# Practica1.net
KiCad netlist of a schematic drawn in EAGLE
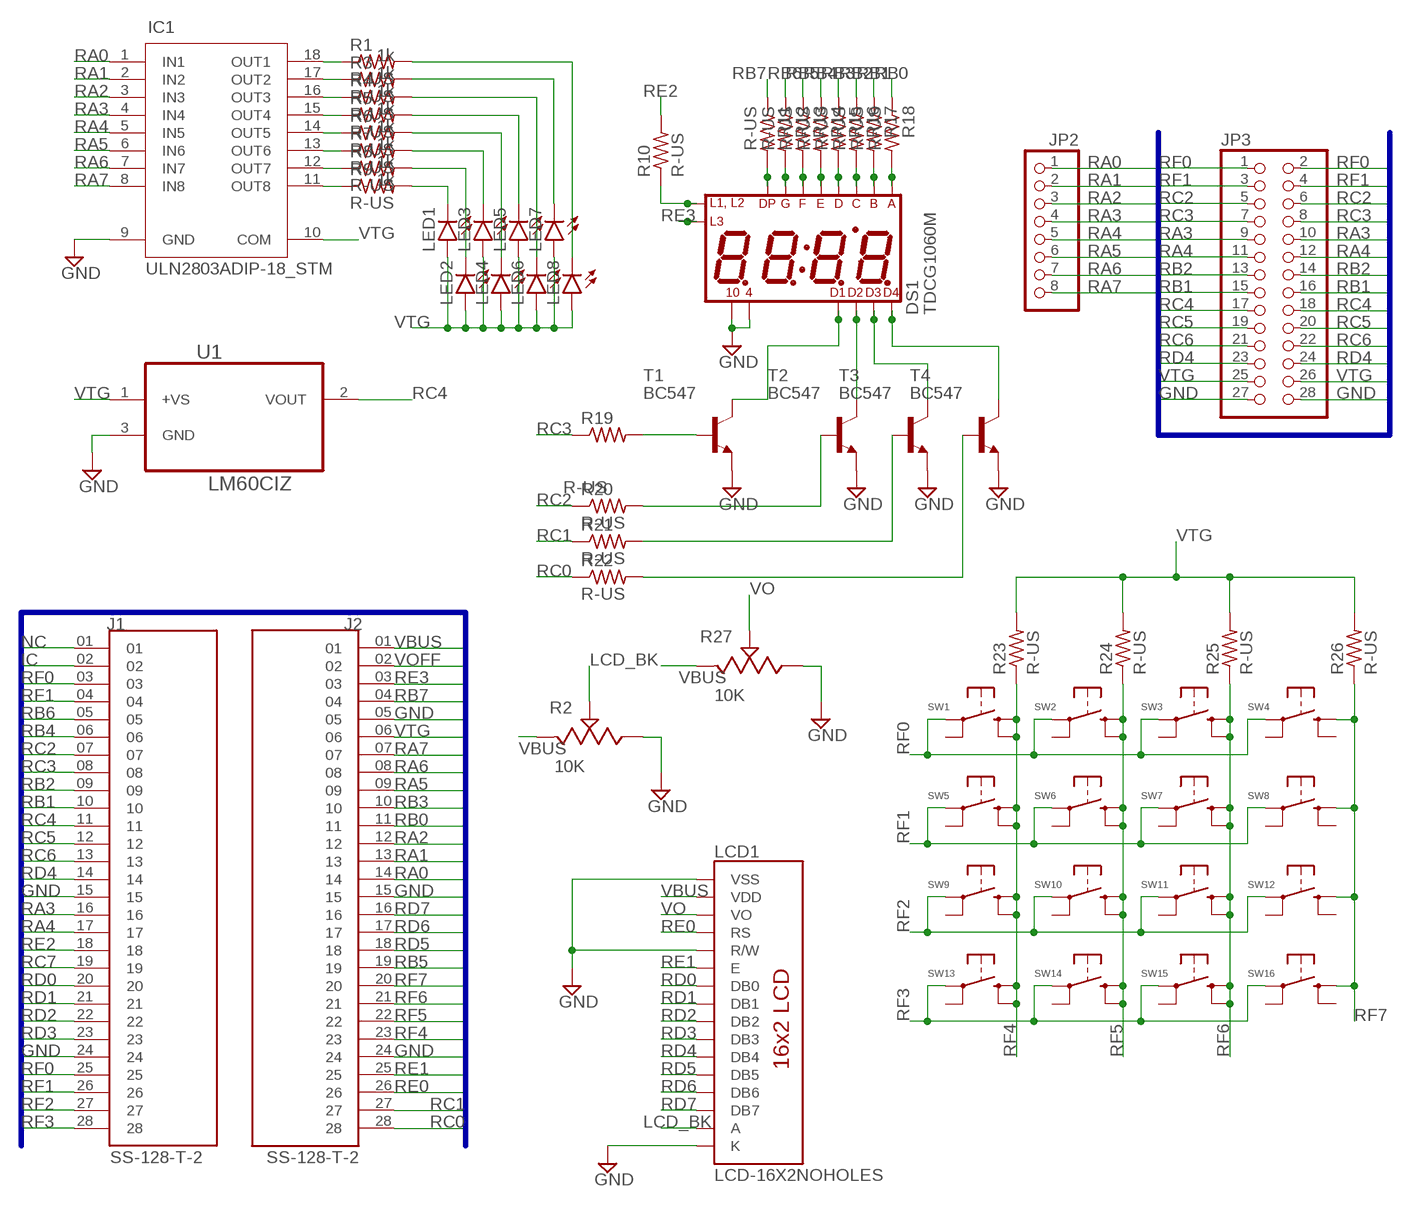
[diagram p0: schematic, sheet 1]

(export (version "E")
  (design (tool "Eeschema 10.0.6"))
  (components
    (comp (ref "DS1")
      (value "TDCG1060M")
      (footprint "eagle-import:DISPLAY_TDCG1060M")
      (fields (field (name "DIGI-KEY_PART_NUMBER") "TDCG1060M-ND") (field (name "MF") "Vishay"))
      (libsource (lib "eagle-import") (part "TDCG1060M"))
    )
    (comp (ref "IC1")
      (value "ULN2803ADIP-18_STM")
      (footprint "eagle-import:DIP-18_STM")
      (fields
        (field (name "MANUFACTURER_PART_NUMBER") "ULN2803A")
        (field (name "COPYRIGHT") "Copyright (C) 2022 Ultra Librarian. All rights reserved.")
      )
      (libsource (lib "eagle-import") (part "ULN2803ADIP-18_STM"))
    )
    (comp (ref "J1")
      (value "SS-128-T-2")
      (footprint "eagle-import:SAMTEC_SS-128-T-2")
      (fields (field (name "DIGI-KEY_PART_NUMBER") "SAM1117-28-ND") (field (name "MF") "Samtec"))
      (libsource (lib "eagle-import") (part "SS-128-T-2"))
    )
    (comp (ref "J2")
      (value "SS-128-T-2")
      (footprint "eagle-import:SAMTEC_SS-128-T-2")
      (fields (field (name "DIGI-KEY_PART_NUMBER") "SAM1117-28-ND") (field (name "MF") "Samtec"))
      (libsource (lib "eagle-import") (part "SS-128-T-2"))
    )
    (comp (ref "JP2")
      (value "PINHD-1X8BIG")
      (footprint "eagle-import:1X08-BIG")
      (libsource (lib "eagle-import") (part "PINHD-1X8BIG"))
    )
    (comp (ref "JP3")
      (value "PINHD-2X14")
      (footprint "eagle-import:2X14")
      (libsource (lib "eagle-import") (part "PINHD-2X14"))
    )
    (comp (ref "LCD1")
      (value "LCD-16X2NOHOLES")
      (footprint "eagle-import:LCD-16X2_NOHOLESNOSILK")
      (libsource (lib "eagle-import") (part "LCD-16X2NOHOLES"))
    )
    (comp (ref "LED1")
      (value "LED3MM")
      (footprint "eagle-import:LED3MM")
      (libsource (lib "eagle-import") (part "LED3MM"))
    )
    (comp (ref "LED2")
      (value "LED3MM")
      (footprint "eagle-import:LED3MM")
      (libsource (lib "eagle-import") (part "LED3MM"))
    )
    (comp (ref "LED3")
      (value "LED3MM")
      (footprint "eagle-import:LED3MM")
      (libsource (lib "eagle-import") (part "LED3MM"))
    )
    (comp (ref "LED4")
      (value "LED3MM")
      (footprint "eagle-import:LED3MM")
      (libsource (lib "eagle-import") (part "LED3MM"))
    )
    (comp (ref "LED5")
      (value "LED3MM")
      (footprint "eagle-import:LED3MM")
      (libsource (lib "eagle-import") (part "LED3MM"))
    )
    (comp (ref "LED6")
      (value "LED3MM")
      (footprint "eagle-import:LED3MM")
      (libsource (lib "eagle-import") (part "LED3MM"))
    )
    (comp (ref "LED7")
      (value "LED3MM")
      (footprint "eagle-import:LED3MM")
      (libsource (lib "eagle-import") (part "LED3MM"))
    )
    (comp (ref "LED8")
      (value "LED3MM")
      (footprint "eagle-import:LED3MM")
      (libsource (lib "eagle-import") (part "LED3MM"))
    )
    (comp (ref "R1")
      (value "R-US")
      (footprint "eagle-import:0207_10")
      (fields (field (name "SPICEPREFIX") "R") (field (name "SPICEPREFIX_1") "1k"))
      (libsource (lib "eagle-import") (part "R-US"))
    )
    (comp (ref "R2")
      (value "10K")
      (footprint "eagle-import:3362P-1-103LF")
      (fields
        (field (name "MANUFACTURER") "Bourns Inc.")
        (field (name "MPN") "3362P-1-103LF")
        (field (name "CREATED_PN") "PCBLayout.com")
      )
      (libsource (lib "eagle-import") (part "3362P-1-103LF"))
    )
    (comp (ref "R3")
      (value "R-US")
      (footprint "eagle-import:0207_10")
      (fields (field (name "SPICEPREFIX") "R") (field (name "SPICEPREFIX_1") "1k"))
      (libsource (lib "eagle-import") (part "R-US"))
    )
    (comp (ref "R4")
      (value "R-US")
      (footprint "eagle-import:0207_10")
      (fields (field (name "SPICEPREFIX") "R") (field (name "SPICEPREFIX_1") "1k"))
      (libsource (lib "eagle-import") (part "R-US"))
    )
    (comp (ref "R5")
      (value "R-US")
      (footprint "eagle-import:0207_10")
      (fields (field (name "SPICEPREFIX") "R") (field (name "SPICEPREFIX_1") "1k"))
      (libsource (lib "eagle-import") (part "R-US"))
    )
    (comp (ref "R6")
      (value "R-US")
      (footprint "eagle-import:0207_10")
      (fields (field (name "SPICEPREFIX") "R") (field (name "SPICEPREFIX_1") "1k"))
      (libsource (lib "eagle-import") (part "R-US"))
    )
    (comp (ref "R7")
      (value "R-US")
      (footprint "eagle-import:0207_10")
      (fields (field (name "SPICEPREFIX") "R") (field (name "SPICEPREFIX_1") "1k"))
      (libsource (lib "eagle-import") (part "R-US"))
    )
    (comp (ref "R8")
      (value "R-US")
      (footprint "eagle-import:0207_10")
      (fields (field (name "SPICEPREFIX") "R") (field (name "SPICEPREFIX_1") "1k"))
      (libsource (lib "eagle-import") (part "R-US"))
    )
    (comp (ref "R9")
      (value "R-US")
      (footprint "eagle-import:0207_10")
      (fields (field (name "SPICEPREFIX") "R") (field (name "SPICEPREFIX_1") "1k"))
      (libsource (lib "eagle-import") (part "R-US"))
    )
    (comp (ref "R10")
      (value "R-US")
      (footprint "eagle-import:0207_10")
      (fields (field (name "SPICEPREFIX") "130"))
      (libsource (lib "eagle-import") (part "R-US"))
    )
    (comp (ref "R11")
      (value "R-US")
      (footprint "eagle-import:0207_10")
      (fields (field (name "SPICEPREFIX") "130"))
      (libsource (lib "eagle-import") (part "R-US"))
    )
    (comp (ref "R12")
      (value "R-US")
      (footprint "eagle-import:0207_10")
      (fields (field (name "SPICEPREFIX") "130"))
      (libsource (lib "eagle-import") (part "R-US"))
    )
    (comp (ref "R13")
      (value "R-US")
      (footprint "eagle-import:0207_10")
      (fields (field (name "SPICEPREFIX") "130"))
      (libsource (lib "eagle-import") (part "R-US"))
    )
    (comp (ref "R14")
      (value "R-US")
      (footprint "eagle-import:0207_10")
      (fields (field (name "SPICEPREFIX") "130"))
      (libsource (lib "eagle-import") (part "R-US"))
    )
    (comp (ref "R15")
      (value "R-US")
      (footprint "eagle-import:0207_10")
      (fields (field (name "SPICEPREFIX") "130"))
      (libsource (lib "eagle-import") (part "R-US"))
    )
    (comp (ref "R16")
      (value "R-US")
      (footprint "eagle-import:0207_10")
      (fields (field (name "SPICEPREFIX") "130"))
      (libsource (lib "eagle-import") (part "R-US"))
    )
    (comp (ref "R17")
      (value "R-US")
      (footprint "eagle-import:0207_10")
      (fields (field (name "SPICEPREFIX") "130"))
      (libsource (lib "eagle-import") (part "R-US"))
    )
    (comp (ref "R18")
      (value "R-US")
      (footprint "eagle-import:0207_10")
      (fields (field (name "SPICEPREFIX") "130"))
      (libsource (lib "eagle-import") (part "R-US"))
    )
    (comp (ref "R19")
      (value "R-US")
      (footprint "eagle-import:0207_10")
      (fields (field (name "SPICEPREFIX") "52K"))
      (libsource (lib "eagle-import") (part "R-US"))
    )
    (comp (ref "R20")
      (value "R-US")
      (footprint "eagle-import:0207_10")
      (fields (field (name "SPICEPREFIX") "52K"))
      (libsource (lib "eagle-import") (part "R-US"))
    )
    (comp (ref "R21")
      (value "R-US")
      (footprint "eagle-import:0207_10")
      (fields (field (name "SPICEPREFIX") "52K"))
      (libsource (lib "eagle-import") (part "R-US"))
    )
    (comp (ref "R22")
      (value "R-US")
      (footprint "eagle-import:0207_10")
      (fields (field (name "SPICEPREFIX") "52K"))
      (libsource (lib "eagle-import") (part "R-US"))
    )
    (comp (ref "R23")
      (value "R-US")
      (footprint "eagle-import:0207_10")
      (fields (field (name "SPICEPREFIX") "1K"))
      (libsource (lib "eagle-import") (part "R-US"))
    )
    (comp (ref "R24")
      (value "R-US")
      (footprint "eagle-import:0207_10")
      (fields (field (name "SPICEPREFIX") "1K"))
      (libsource (lib "eagle-import") (part "R-US"))
    )
    (comp (ref "R25")
      (value "R-US")
      (footprint "eagle-import:0207_10")
      (fields (field (name "SPICEPREFIX") "1K"))
      (libsource (lib "eagle-import") (part "R-US"))
    )
    (comp (ref "R26")
      (value "R-US")
      (footprint "eagle-import:0207_10")
      (fields (field (name "SPICEPREFIX") "1K"))
      (libsource (lib "eagle-import") (part "R-US"))
    )
    (comp (ref "R27")
      (value "10K")
      (footprint "eagle-import:3362P-1-103LF")
      (fields
        (field (name "MANUFACTURER") "Bourns Inc.")
        (field (name "MPN") "3362P-1-103LF")
        (field (name "CREATED_PN") "PCBLayout.com")
      )
      (libsource (lib "eagle-import") (part "3362P-1-103LF"))
    )
    (comp (ref "SW1")
      (value "1825910-2")
      (footprint "eagle-import:TE_1825910-2")
      (fields (field (name "MF") "TE Connectivity"))
      (libsource (lib "eagle-import") (part "1825910-2"))
    )
    (comp (ref "SW2")
      (value "1825910-2")
      (footprint "eagle-import:TE_1825910-2")
      (fields (field (name "MF") "TE Connectivity"))
      (libsource (lib "eagle-import") (part "1825910-2"))
    )
    (comp (ref "SW3")
      (value "1825910-2")
      (footprint "eagle-import:TE_1825910-2")
      (fields (field (name "MF") "TE Connectivity"))
      (libsource (lib "eagle-import") (part "1825910-2"))
    )
    (comp (ref "SW4")
      (value "1825910-2")
      (footprint "eagle-import:TE_1825910-2")
      (fields (field (name "MF") "TE Connectivity"))
      (libsource (lib "eagle-import") (part "1825910-2"))
    )
    (comp (ref "SW5")
      (value "1825910-2")
      (footprint "eagle-import:TE_1825910-2")
      (fields (field (name "MF") "TE Connectivity"))
      (libsource (lib "eagle-import") (part "1825910-2"))
    )
    (comp (ref "SW6")
      (value "1825910-2")
      (footprint "eagle-import:TE_1825910-2")
      (fields (field (name "MF") "TE Connectivity"))
      (libsource (lib "eagle-import") (part "1825910-2"))
    )
    (comp (ref "SW7")
      (value "1825910-2")
      (footprint "eagle-import:TE_1825910-2")
      (fields (field (name "MF") "TE Connectivity"))
      (libsource (lib "eagle-import") (part "1825910-2"))
    )
    (comp (ref "SW8")
      (value "1825910-2")
      (footprint "eagle-import:TE_1825910-2")
      (fields (field (name "MF") "TE Connectivity"))
      (libsource (lib "eagle-import") (part "1825910-2"))
    )
    (comp (ref "SW9")
      (value "1825910-2")
      (footprint "eagle-import:TE_1825910-2")
      (fields (field (name "MF") "TE Connectivity"))
      (libsource (lib "eagle-import") (part "1825910-2"))
    )
    (comp (ref "SW10")
      (value "1825910-2")
      (footprint "eagle-import:TE_1825910-2")
      (fields (field (name "MF") "TE Connectivity"))
      (libsource (lib "eagle-import") (part "1825910-2"))
    )
    (comp (ref "SW11")
      (value "1825910-2")
      (footprint "eagle-import:TE_1825910-2")
      (fields (field (name "MF") "TE Connectivity"))
      (libsource (lib "eagle-import") (part "1825910-2"))
    )
    (comp (ref "SW12")
      (value "1825910-2")
      (footprint "eagle-import:TE_1825910-2")
      (fields (field (name "MF") "TE Connectivity"))
      (libsource (lib "eagle-import") (part "1825910-2"))
    )
    (comp (ref "SW13")
      (value "1825910-2")
      (footprint "eagle-import:TE_1825910-2")
      (fields (field (name "MF") "TE Connectivity"))
      (libsource (lib "eagle-import") (part "1825910-2"))
    )
    (comp (ref "SW14")
      (value "1825910-2")
      (footprint "eagle-import:TE_1825910-2")
      (fields (field (name "MF") "TE Connectivity"))
      (libsource (lib "eagle-import") (part "1825910-2"))
    )
    (comp (ref "SW15")
      (value "1825910-2")
      (footprint "eagle-import:TE_1825910-2")
      (fields (field (name "MF") "TE Connectivity"))
      (libsource (lib "eagle-import") (part "1825910-2"))
    )
    (comp (ref "SW16")
      (value "1825910-2")
      (footprint "eagle-import:TE_1825910-2")
      (fields (field (name "MF") "TE Connectivity"))
      (libsource (lib "eagle-import") (part "1825910-2"))
    )
    (comp (ref "T1")
      (value "BC547")
      (footprint "eagle-import:TO92")
      (libsource (lib "eagle-import") (part "BC547"))
    )
    (comp (ref "T2")
      (value "BC547")
      (footprint "eagle-import:TO92")
      (libsource (lib "eagle-import") (part "BC547"))
    )
    (comp (ref "T3")
      (value "BC547")
      (footprint "eagle-import:TO92")
      (libsource (lib "eagle-import") (part "BC547"))
    )
    (comp (ref "T4")
      (value "BC547")
      (footprint "eagle-import:TO92")
      (libsource (lib "eagle-import") (part "BC547"))
    )
    (comp (ref "U1")
      (value "LM60CIZ")
      (footprint "eagle-import:TO92_")
      (libsource (lib "eagle-import") (part "LM60CIZ"))
    )
  )
  (nets
    (net (code "1") (name "/IC") (class "Default")
      (node (ref "J1") (pin "02") (pinfunction "02_02") (pintype "passive"))
    )
    (net (code "2") (name "/LCD_BK") (class "Default")
      (node (ref "LCD1") (pin "15") (pinfunction "A_15") (pintype "power_in"))
      (node (ref "R2") (pin "2") (pinfunction "2_2") (pintype "passive"))
    )
    (net (code "3") (name "/NC") (class "Default")
      (node (ref "J1") (pin "01") (pinfunction "01_01") (pintype "passive"))
    )
    (net (code "4") (name "/RA0") (class "Default")
      (node (ref "IC1") (pin "1") (pinfunction "IN1_1") (pintype "input"))
      (node (ref "J2") (pin "14") (pinfunction "14_14") (pintype "passive"))
      (node (ref "JP2") (pin "1") (pinfunction "1_1") (pintype "passive"))
    )
    (net (code "5") (name "/RA1") (class "Default")
      (node (ref "IC1") (pin "2") (pinfunction "IN2_2") (pintype "input"))
      (node (ref "J2") (pin "13") (pinfunction "13_13") (pintype "passive"))
      (node (ref "JP2") (pin "2") (pinfunction "2_2") (pintype "passive"))
    )
    (net (code "6") (name "/RA2") (class "Default")
      (node (ref "IC1") (pin "3") (pinfunction "IN3_3") (pintype "input"))
      (node (ref "J2") (pin "12") (pinfunction "12_12") (pintype "passive"))
      (node (ref "JP2") (pin "3") (pinfunction "3_3") (pintype "passive"))
    )
    (net (code "7") (name "/RA3") (class "Default")
      (node (ref "IC1") (pin "4") (pinfunction "IN4_4") (pintype "input"))
      (node (ref "J1") (pin "16") (pinfunction "16_16") (pintype "passive"))
      (node (ref "JP2") (pin "4") (pinfunction "4_4") (pintype "passive"))
      (node (ref "JP3") (pin "10") (pinfunction "10_10") (pintype "passive"))
      (node (ref "JP3") (pin "9") (pinfunction "9_9") (pintype "passive"))
    )
    (net (code "8") (name "/RA4") (class "Default")
      (node (ref "IC1") (pin "5") (pinfunction "IN5_5") (pintype "input"))
      (node (ref "J1") (pin "17") (pinfunction "17_17") (pintype "passive"))
      (node (ref "JP2") (pin "5") (pinfunction "5_5") (pintype "passive"))
      (node (ref "JP3") (pin "11") (pinfunction "11_11") (pintype "passive"))
      (node (ref "JP3") (pin "12") (pinfunction "12_12") (pintype "passive"))
    )
    (net (code "9") (name "/RA5") (class "Default")
      (node (ref "IC1") (pin "6") (pinfunction "IN6_6") (pintype "input"))
      (node (ref "J2") (pin "09") (pinfunction "09_09") (pintype "passive"))
      (node (ref "JP2") (pin "6") (pinfunction "6_6") (pintype "passive"))
    )
    (net (code "10") (name "/RA6") (class "Default")
      (node (ref "IC1") (pin "7") (pinfunction "IN7_7") (pintype "input"))
      (node (ref "J2") (pin "08") (pinfunction "08_08") (pintype "passive"))
      (node (ref "JP2") (pin "7") (pinfunction "7_7") (pintype "passive"))
    )
    (net (code "11") (name "/RA7") (class "Default")
      (node (ref "IC1") (pin "8") (pinfunction "IN8_8") (pintype "input"))
      (node (ref "J2") (pin "07") (pinfunction "07_07") (pintype "passive"))
      (node (ref "JP2") (pin "8") (pinfunction "8_8") (pintype "passive"))
    )
    (net (code "12") (name "/RB0") (class "Default")
      (node (ref "J2") (pin "11") (pinfunction "11_11") (pintype "passive"))
      (node (ref "R18") (pin "1") (pinfunction "1_1") (pintype "passive"))
    )
    (net (code "13") (name "/RB1") (class "Default")
      (node (ref "J1") (pin "10") (pinfunction "10_10") (pintype "passive"))
      (node (ref "JP3") (pin "15") (pinfunction "15_15") (pintype "passive"))
      (node (ref "JP3") (pin "16") (pinfunction "16_16") (pintype "passive"))
      (node (ref "R17") (pin "1") (pinfunction "1_1") (pintype "passive"))
    )
    (net (code "14") (name "/RB2") (class "Default")
      (node (ref "J1") (pin "09") (pinfunction "09_09") (pintype "passive"))
      (node (ref "JP3") (pin "13") (pinfunction "13_13") (pintype "passive"))
      (node (ref "JP3") (pin "14") (pinfunction "14_14") (pintype "passive"))
      (node (ref "R16") (pin "1") (pinfunction "1_1") (pintype "passive"))
    )
    (net (code "15") (name "/RB3") (class "Default")
      (node (ref "J2") (pin "10") (pinfunction "10_10") (pintype "passive"))
      (node (ref "R15") (pin "1") (pinfunction "1_1") (pintype "passive"))
    )
    (net (code "16") (name "/RB4") (class "Default")
      (node (ref "J1") (pin "06") (pinfunction "06_06") (pintype "passive"))
      (node (ref "R14") (pin "1") (pinfunction "1_1") (pintype "passive"))
    )
    (net (code "17") (name "/RB5") (class "Default")
      (node (ref "J2") (pin "19") (pinfunction "19_19") (pintype "passive"))
      (node (ref "R13") (pin "1") (pinfunction "1_1") (pintype "passive"))
    )
    (net (code "18") (name "/RB6") (class "Default")
      (node (ref "J1") (pin "05") (pinfunction "05_05") (pintype "passive"))
      (node (ref "R12") (pin "1") (pinfunction "1_1") (pintype "passive"))
    )
    (net (code "19") (name "/RB7") (class "Default")
      (node (ref "J2") (pin "04") (pinfunction "04_04") (pintype "passive"))
      (node (ref "R11") (pin "1") (pinfunction "1_1") (pintype "passive"))
    )
    (net (code "20") (name "/RC0") (class "Default")
      (node (ref "J2") (pin "28") (pinfunction "28_28") (pintype "passive"))
      (node (ref "R22") (pin "1") (pinfunction "1_1") (pintype "passive"))
    )
    (net (code "21") (name "/RC1") (class "Default")
      (node (ref "J2") (pin "27") (pinfunction "27_27") (pintype "passive"))
      (node (ref "R21") (pin "1") (pinfunction "1_1") (pintype "passive"))
    )
    (net (code "22") (name "/RC2") (class "Default")
      (node (ref "J1") (pin "07") (pinfunction "07_07") (pintype "passive"))
      (node (ref "JP3") (pin "5") (pinfunction "5_5") (pintype "passive"))
      (node (ref "JP3") (pin "6") (pinfunction "6_6") (pintype "passive"))
      (node (ref "R20") (pin "1") (pinfunction "1_1") (pintype "passive"))
    )
    (net (code "23") (name "/RC3") (class "Default")
      (node (ref "J1") (pin "08") (pinfunction "08_08") (pintype "passive"))
      (node (ref "JP3") (pin "7") (pinfunction "7_7") (pintype "passive"))
      (node (ref "JP3") (pin "8") (pinfunction "8_8") (pintype "passive"))
      (node (ref "R19") (pin "1") (pinfunction "1_1") (pintype "passive"))
    )
    (net (code "24") (name "/RC4") (class "Default")
      (node (ref "J1") (pin "11") (pinfunction "11_11") (pintype "passive"))
      (node (ref "JP3") (pin "17") (pinfunction "17_17") (pintype "passive"))
      (node (ref "JP3") (pin "18") (pinfunction "18_18") (pintype "passive"))
      (node (ref "U1") (pin "2") (pinfunction "VOUT_2") (pintype "output"))
    )
    (net (code "25") (name "/RC5") (class "Default")
      (node (ref "J1") (pin "12") (pinfunction "12_12") (pintype "passive"))
      (node (ref "JP3") (pin "19") (pinfunction "19_19") (pintype "passive"))
      (node (ref "JP3") (pin "20") (pinfunction "20_20") (pintype "passive"))
    )
    (net (code "26") (name "/RC6") (class "Default")
      (node (ref "J1") (pin "13") (pinfunction "13_13") (pintype "passive"))
      (node (ref "JP3") (pin "21") (pinfunction "21_21") (pintype "passive"))
      (node (ref "JP3") (pin "22") (pinfunction "22_22") (pintype "passive"))
    )
    (net (code "27") (name "/RC7") (class "Default")
      (node (ref "J1") (pin "19") (pinfunction "19_19") (pintype "passive"))
    )
    (net (code "28") (name "/RD0") (class "Default")
      (node (ref "J1") (pin "20") (pinfunction "20_20") (pintype "passive"))
      (node (ref "LCD1") (pin "7") (pinfunction "DB0_7") (pintype "bidirectional"))
    )
    (net (code "29") (name "/RD1") (class "Default")
      (node (ref "J1") (pin "21") (pinfunction "21_21") (pintype "passive"))
      (node (ref "LCD1") (pin "8") (pinfunction "DB1_8") (pintype "bidirectional"))
    )
    (net (code "30") (name "/RD2") (class "Default")
      (node (ref "J1") (pin "22") (pinfunction "22_22") (pintype "passive"))
      (node (ref "LCD1") (pin "9") (pinfunction "DB2_9") (pintype "bidirectional"))
    )
    (net (code "31") (name "/RD3") (class "Default")
      (node (ref "J1") (pin "23") (pinfunction "23_23") (pintype "passive"))
      (node (ref "LCD1") (pin "10") (pinfunction "DB3_10") (pintype "bidirectional"))
    )
    (net (code "32") (name "/RD4") (class "Default")
      (node (ref "J1") (pin "14") (pinfunction "14_14") (pintype "passive"))
      (node (ref "JP3") (pin "23") (pinfunction "23_23") (pintype "passive"))
      (node (ref "JP3") (pin "24") (pinfunction "24_24") (pintype "passive"))
      (node (ref "LCD1") (pin "11") (pinfunction "DB4_11") (pintype "bidirectional"))
    )
    (net (code "33") (name "/RD5") (class "Default")
      (node (ref "J2") (pin "18") (pinfunction "18_18") (pintype "passive"))
      (node (ref "LCD1") (pin "12") (pinfunction "DB5_12") (pintype "bidirectional"))
    )
    (net (code "34") (name "/RD6") (class "Default")
      (node (ref "J2") (pin "17") (pinfunction "17_17") (pintype "passive"))
      (node (ref "LCD1") (pin "13") (pinfunction "DB6_13") (pintype "bidirectional"))
    )
    (net (code "35") (name "/RD7") (class "Default")
      (node (ref "J2") (pin "16") (pinfunction "16_16") (pintype "passive"))
      (node (ref "LCD1") (pin "14") (pinfunction "DB7_14") (pintype "bidirectional"))
    )
    (net (code "36") (name "/RE0") (class "Default")
      (node (ref "J2") (pin "26") (pinfunction "26_26") (pintype "passive"))
      (node (ref "LCD1") (pin "4") (pinfunction "RS_4") (pintype "input"))
    )
    (net (code "37") (name "/RE1") (class "Default")
      (node (ref "J2") (pin "25") (pinfunction "25_25") (pintype "passive"))
      (node (ref "LCD1") (pin "6") (pinfunction "E_6") (pintype "input"))
    )
    (net (code "38") (name "/RE2") (class "Default")
      (node (ref "J1") (pin "18") (pinfunction "18_18") (pintype "passive"))
      (node (ref "R10") (pin "2") (pinfunction "2_2") (pintype "passive"))
    )
    (net (code "39") (name "/RE3") (class "Default")
      (node (ref "DS1") (pin "9") (pinfunction "L3_9") (pintype "passive"))
      (node (ref "J2") (pin "03") (pinfunction "03_03") (pintype "passive"))
    )
    (net (code "40") (name "/RF0") (class "Default")
      (node (ref "J1") (pin "03") (pinfunction "03_03") (pintype "passive"))
      (node (ref "J1") (pin "25") (pinfunction "25_25") (pintype "passive"))
      (node (ref "JP3") (pin "1") (pinfunction "1_1") (pintype "passive"))
      (node (ref "JP3") (pin "2") (pinfunction "2_2") (pintype "passive"))
      (node (ref "SW1") (pin "1") (pinfunction "P_1") (pintype "passive"))
      (node (ref "SW2") (pin "1") (pinfunction "P_1") (pintype "passive"))
      (node (ref "SW3") (pin "1") (pinfunction "P_1") (pintype "passive"))
      (node (ref "SW4") (pin "1") (pinfunction "P_1") (pintype "passive"))
    )
    (net (code "41") (name "/RF1") (class "Default")
      (node (ref "J1") (pin "04") (pinfunction "04_04") (pintype "passive"))
      (node (ref "J1") (pin "26") (pinfunction "26_26") (pintype "passive"))
      (node (ref "JP3") (pin "3") (pinfunction "3_3") (pintype "passive"))
      (node (ref "JP3") (pin "4") (pinfunction "4_4") (pintype "passive"))
      (node (ref "SW5") (pin "1") (pinfunction "P_1") (pintype "passive"))
      (node (ref "SW6") (pin "1") (pinfunction "P_1") (pintype "passive"))
      (node (ref "SW7") (pin "1") (pinfunction "P_1") (pintype "passive"))
      (node (ref "SW8") (pin "1") (pinfunction "P_1") (pintype "passive"))
    )
    (net (code "42") (name "/RF2") (class "Default")
      (node (ref "J1") (pin "27") (pinfunction "27_27") (pintype "passive"))
      (node (ref "SW10") (pin "1") (pinfunction "P_1") (pintype "passive"))
      (node (ref "SW11") (pin "1") (pinfunction "P_1") (pintype "passive"))
      (node (ref "SW12") (pin "1") (pinfunction "P_1") (pintype "passive"))
      (node (ref "SW9") (pin "1") (pinfunction "P_1") (pintype "passive"))
    )
    (net (code "43") (name "/RF3") (class "Default")
      (node (ref "J1") (pin "28") (pinfunction "28_28") (pintype "passive"))
      (node (ref "SW13") (pin "1") (pinfunction "P_1") (pintype "passive"))
      (node (ref "SW14") (pin "1") (pinfunction "P_1") (pintype "passive"))
      (node (ref "SW15") (pin "1") (pinfunction "P_1") (pintype "passive"))
      (node (ref "SW16") (pin "1") (pinfunction "P_1") (pintype "passive"))
    )
    (net (code "44") (name "/RF4") (class "Default")
      (node (ref "J2") (pin "23") (pinfunction "23_23") (pintype "passive"))
      (node (ref "R23") (pin "1") (pinfunction "1_1") (pintype "passive"))
      (node (ref "SW1") (pin "2") (pinfunction "S_2") (pintype "passive"))
      (node (ref "SW1") (pin "4") (pinfunction "S1_4") (pintype "passive"))
      (node (ref "SW13") (pin "2") (pinfunction "S_2") (pintype "passive"))
      (node (ref "SW13") (pin "4") (pinfunction "S1_4") (pintype "passive"))
      (node (ref "SW5") (pin "2") (pinfunction "S_2") (pintype "passive"))
      (node (ref "SW5") (pin "4") (pinfunction "S1_4") (pintype "passive"))
      (node (ref "SW9") (pin "2") (pinfunction "S_2") (pintype "passive"))
      (node (ref "SW9") (pin "4") (pinfunction "S1_4") (pintype "passive"))
    )
    (net (code "45") (name "/RF5") (class "Default")
      (node (ref "J2") (pin "22") (pinfunction "22_22") (pintype "passive"))
      (node (ref "R24") (pin "1") (pinfunction "1_1") (pintype "passive"))
      (node (ref "SW10") (pin "2") (pinfunction "S_2") (pintype "passive"))
      (node (ref "SW10") (pin "4") (pinfunction "S1_4") (pintype "passive"))
      (node (ref "SW14") (pin "2") (pinfunction "S_2") (pintype "passive"))
      (node (ref "SW14") (pin "4") (pinfunction "S1_4") (pintype "passive"))
      (node (ref "SW2") (pin "2") (pinfunction "S_2") (pintype "passive"))
      (node (ref "SW2") (pin "4") (pinfunction "S1_4") (pintype "passive"))
      (node (ref "SW6") (pin "2") (pinfunction "S_2") (pintype "passive"))
      (node (ref "SW6") (pin "4") (pinfunction "S1_4") (pintype "passive"))
    )
    (net (code "46") (name "/RF6") (class "Default")
      (node (ref "J2") (pin "21") (pinfunction "21_21") (pintype "passive"))
      (node (ref "R25") (pin "1") (pinfunction "1_1") (pintype "passive"))
      (node (ref "SW11") (pin "2") (pinfunction "S_2") (pintype "passive"))
      (node (ref "SW11") (pin "4") (pinfunction "S1_4") (pintype "passive"))
      (node (ref "SW15") (pin "2") (pinfunction "S_2") (pintype "passive"))
      (node (ref "SW15") (pin "4") (pinfunction "S1_4") (pintype "passive"))
      (node (ref "SW3") (pin "2") (pinfunction "S_2") (pintype "passive"))
      (node (ref "SW3") (pin "4") (pinfunction "S1_4") (pintype "passive"))
      (node (ref "SW7") (pin "2") (pinfunction "S_2") (pintype "passive"))
      (node (ref "SW7") (pin "4") (pinfunction "S1_4") (pintype "passive"))
    )
    (net (code "47") (name "/RF7") (class "Default")
      (node (ref "J2") (pin "20") (pinfunction "20_20") (pintype "passive"))
      (node (ref "R26") (pin "1") (pinfunction "1_1") (pintype "passive"))
      (node (ref "SW12") (pin "2") (pinfunction "S_2") (pintype "passive"))
      (node (ref "SW16") (pin "2") (pinfunction "S_2") (pintype "passive"))
      (node (ref "SW4") (pin "2") (pinfunction "S_2") (pintype "passive"))
      (node (ref "SW8") (pin "2") (pinfunction "S_2") (pintype "passive"))
    )
    (net (code "48") (name "/VBUS") (class "Default")
      (node (ref "J2") (pin "01") (pinfunction "01_01") (pintype "passive"))
      (node (ref "LCD1") (pin "2") (pinfunction "VDD_2") (pintype "power_in"))
      (node (ref "R2") (pin "1") (pinfunction "1_1") (pintype "passive"))
      (node (ref "R27") (pin "1") (pinfunction "1_1") (pintype "passive"))
    )
    (net (code "49") (name "/VO") (class "Default")
      (node (ref "LCD1") (pin "3") (pinfunction "VO_3") (pintype "bidirectional"))
      (node (ref "R27") (pin "2") (pinfunction "2_2") (pintype "passive"))
    )
    (net (code "50") (name "/VOFF") (class "Default")
      (node (ref "J2") (pin "02") (pinfunction "02_02") (pintype "passive"))
    )
    (net (code "51") (name "/VTG") (class "Default")
      (node (ref "IC1") (pin "10") (pinfunction "COM_10") (pintype "passive"))
      (node (ref "J2") (pin "06") (pinfunction "06_06") (pintype "passive"))
      (node (ref "JP3") (pin "25") (pinfunction "25_25") (pintype "passive"))
      (node (ref "JP3") (pin "26") (pinfunction "26_26") (pintype "passive"))
      (node (ref "LED1") (pin "A") (pinfunction "A_A") (pintype "passive"))
      (node (ref "LED2") (pin "A") (pinfunction "A_A") (pintype "passive"))
      (node (ref "LED3") (pin "A") (pinfunction "A_A") (pintype "passive"))
      (node (ref "LED4") (pin "A") (pinfunction "A_A") (pintype "passive"))
      (node (ref "LED5") (pin "A") (pinfunction "A_A") (pintype "passive"))
      (node (ref "LED6") (pin "A") (pinfunction "A_A") (pintype "passive"))
      (node (ref "LED7") (pin "A") (pinfunction "A_A") (pintype "passive"))
      (node (ref "LED8") (pin "A") (pinfunction "A_A") (pintype "passive"))
      (node (ref "R23") (pin "2") (pinfunction "2_2") (pintype "passive"))
      (node (ref "R24") (pin "2") (pinfunction "2_2") (pintype "passive"))
      (node (ref "R25") (pin "2") (pinfunction "2_2") (pintype "passive"))
      (node (ref "R26") (pin "2") (pinfunction "2_2") (pintype "passive"))
      (node (ref "U1") (pin "1") (pinfunction "+VS_1") (pintype "power_in"))
    )
    (net (code "52") (name "GND") (class "Default")
      (node (ref "DS1") (pin "10") (pinfunction "10_10") (pintype "passive"))
      (node (ref "DS1") (pin "4") (pinfunction "4_4") (pintype "passive"))
      (node (ref "IC1") (pin "9") (pinfunction "GND_9") (pintype "power_in"))
      (node (ref "J1") (pin "15") (pinfunction "15_15") (pintype "passive"))
      (node (ref "J1") (pin "24") (pinfunction "24_24") (pintype "passive"))
      (node (ref "J2") (pin "05") (pinfunction "05_05") (pintype "passive"))
      (node (ref "J2") (pin "15") (pinfunction "15_15") (pintype "passive"))
      (node (ref "J2") (pin "24") (pinfunction "24_24") (pintype "passive"))
      (node (ref "JP3") (pin "27") (pinfunction "27_27") (pintype "passive"))
      (node (ref "JP3") (pin "28") (pinfunction "28_28") (pintype "passive"))
      (node (ref "LCD1") (pin "1") (pinfunction "VSS_1") (pintype "power_in"))
      (node (ref "LCD1") (pin "16") (pinfunction "K_16") (pintype "power_in"))
      (node (ref "LCD1") (pin "5") (pinfunction "R/W_5") (pintype "input"))
      (node (ref "R2") (pin "3") (pinfunction "3_3") (pintype "passive"))
      (node (ref "R27") (pin "3") (pinfunction "3_3") (pintype "passive"))
      (node (ref "T1") (pin "1") (pinfunction "E_1") (pintype "passive"))
      (node (ref "T2") (pin "1") (pinfunction "E_1") (pintype "passive"))
      (node (ref "T3") (pin "1") (pinfunction "E_1") (pintype "passive"))
      (node (ref "T4") (pin "1") (pinfunction "E_1") (pintype "passive"))
      (node (ref "U1") (pin "3") (pinfunction "GND_3") (pintype "passive"))
    )
    (net (code "53") (name "Net-(DS1-A)") (class "Default")
      (node (ref "DS1") (pin "14") (pinfunction "A_14") (pintype "passive"))
      (node (ref "R18") (pin "2") (pinfunction "2_2") (pintype "passive"))
    )
    (net (code "54") (name "Net-(DS1-B)") (class "Default")
      (node (ref "DS1") (pin "16") (pinfunction "B_16") (pintype "passive"))
      (node (ref "R17") (pin "2") (pinfunction "2_2") (pintype "passive"))
    )
    (net (code "55") (name "Net-(DS1-C)") (class "Default")
      (node (ref "DS1") (pin "13") (pinfunction "C_13") (pintype "passive"))
      (node (ref "R16") (pin "2") (pinfunction "2_2") (pintype "passive"))
    )
    (net (code "56") (name "Net-(DS1-D)") (class "Default")
      (node (ref "DS1") (pin "3") (pinfunction "D_3") (pintype "passive"))
      (node (ref "R15") (pin "2") (pinfunction "2_2") (pintype "passive"))
    )
    (net (code "57") (name "Net-(DS1-DIG1)") (class "Default")
      (node (ref "DS1") (pin "1") (pinfunction "DIG1_1") (pintype "passive"))
      (node (ref "T1") (pin "3") (pinfunction "C_3") (pintype "passive"))
    )
    (net (code "58") (name "Net-(DS1-DIG2)") (class "Default")
      (node (ref "DS1") (pin "2") (pinfunction "DIG2_2") (pintype "passive"))
      (node (ref "T2") (pin "3") (pinfunction "C_3") (pintype "passive"))
    )
    (net (code "59") (name "Net-(DS1-DIG3)") (class "Default")
      (node (ref "DS1") (pin "6") (pinfunction "DIG3_6") (pintype "passive"))
      (node (ref "T3") (pin "3") (pinfunction "C_3") (pintype "passive"))
    )
    (net (code "60") (name "Net-(DS1-DIG4)") (class "Default")
      (node (ref "DS1") (pin "8") (pinfunction "DIG4_8") (pintype "passive"))
      (node (ref "T4") (pin "3") (pinfunction "C_3") (pintype "passive"))
    )
    (net (code "61") (name "Net-(DS1-DP)") (class "Default")
      (node (ref "DS1") (pin "7") (pinfunction "DP_7") (pintype "passive"))
      (node (ref "R11") (pin "2") (pinfunction "2_2") (pintype "passive"))
    )
    (net (code "62") (name "Net-(DS1-E)") (class "Default")
      (node (ref "DS1") (pin "5") (pinfunction "E_5") (pintype "passive"))
      (node (ref "R14") (pin "2") (pinfunction "2_2") (pintype "passive"))
    )
    (net (code "63") (name "Net-(DS1-F)") (class "Default")
      (node (ref "DS1") (pin "11") (pinfunction "F_11") (pintype "passive"))
      (node (ref "R13") (pin "2") (pinfunction "2_2") (pintype "passive"))
    )
    (net (code "64") (name "Net-(DS1-G)") (class "Default")
      (node (ref "DS1") (pin "15") (pinfunction "G_15") (pintype "passive"))
      (node (ref "R12") (pin "2") (pinfunction "2_2") (pintype "passive"))
    )
    (net (code "65") (name "Net-(DS1-L1_L2)") (class "Default")
      (node (ref "DS1") (pin "12") (pinfunction "L1_L2_12") (pintype "passive"))
      (node (ref "R10") (pin "1") (pinfunction "1_1") (pintype "passive"))
    )
    (net (code "66") (name "Net-(IC1-OUT1)") (class "Default")
      (node (ref "IC1") (pin "18") (pinfunction "OUT1_18") (pintype "passive"))
      (node (ref "R1") (pin "1") (pinfunction "1_1") (pintype "passive"))
    )
    (net (code "67") (name "Net-(IC1-OUT2)") (class "Default")
      (node (ref "IC1") (pin "17") (pinfunction "OUT2_17") (pintype "passive"))
      (node (ref "R3") (pin "1") (pinfunction "1_1") (pintype "passive"))
    )
    (net (code "68") (name "Net-(IC1-OUT3)") (class "Default")
      (node (ref "IC1") (pin "16") (pinfunction "OUT3_16") (pintype "passive"))
      (node (ref "R4") (pin "1") (pinfunction "1_1") (pintype "passive"))
    )
    (net (code "69") (name "Net-(IC1-OUT4)") (class "Default")
      (node (ref "IC1") (pin "15") (pinfunction "OUT4_15") (pintype "passive"))
      (node (ref "R5") (pin "1") (pinfunction "1_1") (pintype "passive"))
    )
    (net (code "70") (name "Net-(IC1-OUT5)") (class "Default")
      (node (ref "IC1") (pin "14") (pinfunction "OUT5_14") (pintype "passive"))
      (node (ref "R6") (pin "1") (pinfunction "1_1") (pintype "passive"))
    )
    (net (code "71") (name "Net-(IC1-OUT6)") (class "Default")
      (node (ref "IC1") (pin "13") (pinfunction "OUT6_13") (pintype "passive"))
      (node (ref "R7") (pin "1") (pinfunction "1_1") (pintype "passive"))
    )
    (net (code "72") (name "Net-(IC1-OUT7)") (class "Default")
      (node (ref "IC1") (pin "12") (pinfunction "OUT7_12") (pintype "passive"))
      (node (ref "R8") (pin "1") (pinfunction "1_1") (pintype "passive"))
    )
    (net (code "73") (name "Net-(IC1-OUT8)") (class "Default")
      (node (ref "IC1") (pin "11") (pinfunction "OUT8_11") (pintype "passive"))
      (node (ref "R9") (pin "1") (pinfunction "1_1") (pintype "passive"))
    )
    (net (code "74") (name "Net-(LED1-C)") (class "Default")
      (node (ref "LED1") (pin "K") (pinfunction "C_K") (pintype "passive"))
      (node (ref "R9") (pin "2") (pinfunction "2_2") (pintype "passive"))
    )
    (net (code "75") (name "Net-(LED2-C)") (class "Default")
      (node (ref "LED2") (pin "K") (pinfunction "C_K") (pintype "passive"))
      (node (ref "R8") (pin "2") (pinfunction "2_2") (pintype "passive"))
    )
    (net (code "76") (name "Net-(LED3-C)") (class "Default")
      (node (ref "LED3") (pin "K") (pinfunction "C_K") (pintype "passive"))
      (node (ref "R7") (pin "2") (pinfunction "2_2") (pintype "passive"))
    )
    (net (code "77") (name "Net-(LED4-C)") (class "Default")
      (node (ref "LED4") (pin "K") (pinfunction "C_K") (pintype "passive"))
      (node (ref "R6") (pin "2") (pinfunction "2_2") (pintype "passive"))
    )
    (net (code "78") (name "Net-(LED5-C)") (class "Default")
      (node (ref "LED5") (pin "K") (pinfunction "C_K") (pintype "passive"))
      (node (ref "R5") (pin "2") (pinfunction "2_2") (pintype "passive"))
    )
    (net (code "79") (name "Net-(LED6-C)") (class "Default")
      (node (ref "LED6") (pin "K") (pinfunction "C_K") (pintype "passive"))
      (node (ref "R4") (pin "2") (pinfunction "2_2") (pintype "passive"))
    )
    (net (code "80") (name "Net-(LED7-C)") (class "Default")
      (node (ref "LED7") (pin "K") (pinfunction "C_K") (pintype "passive"))
      (node (ref "R3") (pin "2") (pinfunction "2_2") (pintype "passive"))
    )
    (net (code "81") (name "Net-(LED8-C)") (class "Default")
      (node (ref "LED8") (pin "K") (pinfunction "C_K") (pintype "passive"))
      (node (ref "R1") (pin "2") (pinfunction "2_2") (pintype "passive"))
    )
    (net (code "82") (name "Net-(T1-B)") (class "Default")
      (node (ref "R19") (pin "2") (pinfunction "2_2") (pintype "passive"))
      (node (ref "T1") (pin "2") (pinfunction "B_2") (pintype "passive"))
    )
    (net (code "83") (name "Net-(T2-B)") (class "Default")
      (node (ref "R20") (pin "2") (pinfunction "2_2") (pintype "passive"))
      (node (ref "T2") (pin "2") (pinfunction "B_2") (pintype "passive"))
    )
    (net (code "84") (name "Net-(T3-B)") (class "Default")
      (node (ref "R21") (pin "2") (pinfunction "2_2") (pintype "passive"))
      (node (ref "T3") (pin "2") (pinfunction "B_2") (pintype "passive"))
    )
    (net (code "85") (name "Net-(T4-B)") (class "Default")
      (node (ref "R22") (pin "2") (pinfunction "2_2") (pintype "passive"))
      (node (ref "T4") (pin "2") (pinfunction "B_2") (pintype "passive"))
    )
    (net (code "86") (name "unconnected-(SW1-P1-Pad3)") (class "Default")
      (node (ref "SW1") (pin "3") (pinfunction "P1_3") (pintype "passive"))
    )
    (net (code "87") (name "unconnected-(SW2-P1-Pad3)") (class "Default")
      (node (ref "SW2") (pin "3") (pinfunction "P1_3") (pintype "passive"))
    )
    (net (code "88") (name "unconnected-(SW3-P1-Pad3)") (class "Default")
      (node (ref "SW3") (pin "3") (pinfunction "P1_3") (pintype "passive"))
    )
    (net (code "89") (name "unconnected-(SW4-P1-Pad3)") (class "Default")
      (node (ref "SW4") (pin "3") (pinfunction "P1_3") (pintype "passive"))
    )
    (net (code "90") (name "unconnected-(SW4-S1-Pad4)") (class "Default")
      (node (ref "SW4") (pin "4") (pinfunction "S1_4") (pintype "passive"))
    )
    (net (code "91") (name "unconnected-(SW5-P1-Pad3)") (class "Default")
      (node (ref "SW5") (pin "3") (pinfunction "P1_3") (pintype "passive"))
    )
    (net (code "92") (name "unconnected-(SW6-P1-Pad3)") (class "Default")
      (node (ref "SW6") (pin "3") (pinfunction "P1_3") (pintype "passive"))
    )
    (net (code "93") (name "unconnected-(SW7-P1-Pad3)") (class "Default")
      (node (ref "SW7") (pin "3") (pinfunction "P1_3") (pintype "passive"))
    )
    (net (code "94") (name "unconnected-(SW8-P1-Pad3)") (class "Default")
      (node (ref "SW8") (pin "3") (pinfunction "P1_3") (pintype "passive"))
    )
    (net (code "95") (name "unconnected-(SW8-S1-Pad4)") (class "Default")
      (node (ref "SW8") (pin "4") (pinfunction "S1_4") (pintype "passive"))
    )
    (net (code "96") (name "unconnected-(SW9-P1-Pad3)") (class "Default")
      (node (ref "SW9") (pin "3") (pinfunction "P1_3") (pintype "passive"))
    )
    (net (code "97") (name "unconnected-(SW10-P1-Pad3)") (class "Default")
      (node (ref "SW10") (pin "3") (pinfunction "P1_3") (pintype "passive"))
    )
    (net (code "98") (name "unconnected-(SW11-P1-Pad3)") (class "Default")
      (node (ref "SW11") (pin "3") (pinfunction "P1_3") (pintype "passive"))
    )
    (net (code "99") (name "unconnected-(SW12-P1-Pad3)") (class "Default")
      (node (ref "SW12") (pin "3") (pinfunction "P1_3") (pintype "passive"))
    )
    (net (code "100") (name "unconnected-(SW12-S1-Pad4)") (class "Default")
      (node (ref "SW12") (pin "4") (pinfunction "S1_4") (pintype "passive"))
    )
    (net (code "101") (name "unconnected-(SW13-P1-Pad3)") (class "Default")
      (node (ref "SW13") (pin "3") (pinfunction "P1_3") (pintype "passive"))
    )
    (net (code "102") (name "unconnected-(SW14-P1-Pad3)") (class "Default")
      (node (ref "SW14") (pin "3") (pinfunction "P1_3") (pintype "passive"))
    )
    (net (code "103") (name "unconnected-(SW15-P1-Pad3)") (class "Default")
      (node (ref "SW15") (pin "3") (pinfunction "P1_3") (pintype "passive"))
    )
    (net (code "104") (name "unconnected-(SW16-P1-Pad3)") (class "Default")
      (node (ref "SW16") (pin "3") (pinfunction "P1_3") (pintype "passive"))
    )
    (net (code "105") (name "unconnected-(SW16-S1-Pad4)") (class "Default")
      (node (ref "SW16") (pin "4") (pinfunction "S1_4") (pintype "passive"))
    )
  )
)
